# MCU.net
KiCad netlist of a schematic drawn in Altium Designer
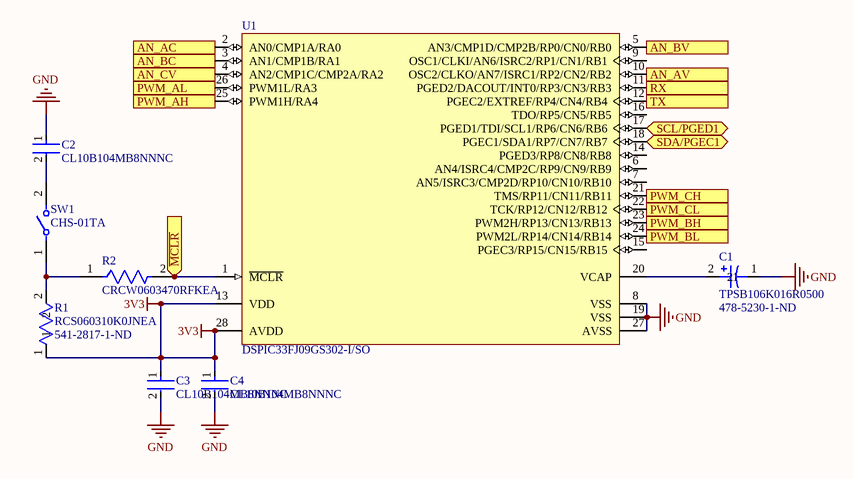
[diagram p0: MCU.SchDoc]

(export (version "E")
  (design (tool "Eeschema 10.0.6"))
  (components
    (comp (ref "C1")
      (value "TPSB106K016R0500")
      (footprint "TPSB106K016R0500")
      (description "CAP TANT 10UF 10% 16V SMD")
      (fields
        (field (name "MANUFACTURER") "Kyocera AVX")
        (field (name "TOLERANCE") "10%")
        (field (name "SUPPLIER PART NUMBER 1") "478-5230-1-ND")
      )
      (libsource (lib "Schematic Library") (part "TPSB106K016R0500"))
    )
    (comp (ref "C2")
      (value "CL10B104MB8NNNC")
      (footprint "FP-CL10-IPC_C")
      (description "Cap Ceramic 100nF 50V X7R ±20% Pad SMD 0603 +125°C T/R")
      (fields (field (name "TOLERANCE") "20%"))
      (libsource (lib "Altium Content Vault") (part "b4654b650e69147ec39a6b967a45e02"))
    )
    (comp (ref "C3")
      (value "CL10B104MB8NNNC")
      (footprint "FP-CL10-IPC_C")
      (description "Cap Ceramic 100nF 50V X7R ±20% Pad SMD 0603 +125°C T/R")
      (fields (field (name "TOLERANCE") "20%"))
      (libsource (lib "Altium Content Vault") (part "b4654b650e69147ec39a6b967a45e02"))
    )
    (comp (ref "C4")
      (value "CL10B104MB8NNNC")
      (footprint "FP-CL10-IPC_C")
      (description "Cap Ceramic 100nF 50V X7R ±20% Pad SMD 0603 +125°C T/R")
      (fields (field (name "TOLERANCE") "20%"))
      (libsource (lib "Altium Content Vault") (part "b4654b650e69147ec39a6b967a45e02"))
    )
    (comp (ref "R1")
      (value "RCS060310K0JNEA")
      (footprint "RCS060310K0JNEA")
      (description "RES SMD 10K OHM 5% 1/4W 0603")
      (fields
        (field (name "MANUFACTURER") "Vishay Dale")
        (field (name "TOLERANCE") "5%")
        (field (name "SUPPLIER PART NUMBER 1") "541-2817-1-ND")
      )
      (libsource (lib "Schematic Library") (part "RCS060310K0JNEA"))
    )
    (comp (ref "R2")
      (value "CRCW0603470RFKEA")
      (footprint "FP-CRCW0603-e3-MFG")
      (description "RES Thick Film, 470Ω, 1%, 0.1W, 100ppm/°C, 0603")
      (fields (field (name "TOLERANCE") "1%"))
      (libsource (lib "Altium Content Vault") (part "1029c3af85768c4190bb7ad29bc67b5"))
    )
    (comp (ref "SW1")
      (value "CHS-01TA")
      (footprint "FP-CHS-01TA-MFG")
      (description "SWITCH SLIDE DIP SPST 100MA 6V")
      (fields
        (field (name "OCTOPART") "https://octopart.com/chs-01ta-nidec+copal-52304644")
        (field (name "MANUFACTURER") "Nidec Copal Electronics")
      )
      (libsource (lib "Altium Content Vault") (part "bb27bde45df87f1f469753f287ef5ae"))
    )
    (comp (ref "U1")
      (value "DSPIC33FJ09GS302-I/SO")
      (footprint "MCHP-SOIC-SO28_M")
      (fields (field (name "MANUFACTURER") "Microchip"))
      (libsource (lib "Altium Content Vault") (part "MCHP-dsPIC33FJ09GS302-SOIC_SPDIP_SSOP-28"))
    )
  )
  (nets
    (net (code "1") (name "/AN_AC") (class "Default")
      (node (ref "U1") (pin "2") (pinfunction "AN0/CMP1A/RA0_2") (pintype "bidirectional"))
    )
    (net (code "2") (name "/AN_AV") (class "Default")
      (node (ref "U1") (pin "10") (pinfunction "OSC2/CLKO/AN7/ISRC1/RP2/CN2/RB2_10") (pintype "bidirectional"))
    )
    (net (code "3") (name "/AN_BC") (class "Default")
      (node (ref "U1") (pin "3") (pinfunction "AN1/CMP1B/RA1_3") (pintype "bidirectional"))
    )
    (net (code "4") (name "/AN_BV") (class "Default")
      (node (ref "U1") (pin "5") (pinfunction "AN3/CMP1D/CMP2B/RP0/CN0/RB0_5") (pintype "bidirectional"))
    )
    (net (code "5") (name "/AN_CV") (class "Default")
      (node (ref "U1") (pin "4") (pinfunction "AN2/CMP1C/CMP2A/RA2_4") (pintype "bidirectional"))
    )
    (net (code "6") (name "/PWM_AH") (class "Default")
      (node (ref "U1") (pin "25") (pinfunction "PWM1H/RA4_25") (pintype "bidirectional"))
    )
    (net (code "7") (name "/PWM_AL") (class "Default")
      (node (ref "U1") (pin "26") (pinfunction "PWM1L/RA3_26") (pintype "bidirectional"))
    )
    (net (code "8") (name "/PWM_BH") (class "Default")
      (node (ref "U1") (pin "23") (pinfunction "PWM2H/RP13/CN13/RB13_23") (pintype "bidirectional"))
    )
    (net (code "9") (name "/PWM_BL") (class "Default")
      (node (ref "U1") (pin "24") (pinfunction "PWM2L/RP14/CN14/RB14_24") (pintype "bidirectional"))
    )
    (net (code "10") (name "/PWM_CH") (class "Default")
      (node (ref "U1") (pin "21") (pinfunction "TMS/RP11/CN11/RB11_21") (pintype "bidirectional"))
    )
    (net (code "11") (name "/PWM_CL") (class "Default")
      (node (ref "U1") (pin "22") (pinfunction "TCK/RP12/CN12/RB12_22") (pintype "bidirectional"))
    )
    (net (code "12") (name "/RX") (class "Default")
      (node (ref "U1") (pin "11") (pinfunction "PGED2/DACOUT/INT0/RP3/CN3/RB3_11") (pintype "bidirectional"))
    )
    (net (code "13") (name "/SCL{slash}PGED1") (class "Default")
      (node (ref "U1") (pin "17") (pinfunction "PGED1/TDI/SCL1/RP6/CN6/RB6_17") (pintype "bidirectional"))
    )
    (net (code "14") (name "/SDA{slash}PGEC1") (class "Default")
      (node (ref "U1") (pin "18") (pinfunction "PGEC1/SDA1/RP7/CN7/RB7_18") (pintype "bidirectional"))
    )
    (net (code "15") (name "/TX") (class "Default")
      (node (ref "U1") (pin "12") (pinfunction "PGEC2/EXTREF/RP4/CN4/RB4_12") (pintype "bidirectional"))
    )
    (net (code "16") (name "/~{MCLR}") (class "Default")
      (node (ref "R2") (pin "2") (pinfunction "2_2") (pintype "passive"))
      (node (ref "U1") (pin "1") (pinfunction "~{MCLR}_1") (pintype "input"))
    )
    (net (code "17") (name "3V3") (class "Default")
      (node (ref "C3") (pin "1") (pinfunction "1_1") (pintype "passive"))
      (node (ref "C4") (pin "1") (pinfunction "1_1") (pintype "passive"))
      (node (ref "R1") (pin "1") (pinfunction "1_1") (pintype "passive"))
      (node (ref "U1") (pin "13") (pinfunction "VDD_13") (pintype "power_in"))
      (node (ref "U1") (pin "28") (pinfunction "AVDD_28") (pintype "power_in"))
    )
    (net (code "18") (name "GND") (class "Default")
      (node (ref "C1") (pin "1") (pinfunction "1_1") (pintype "passive"))
      (node (ref "C2") (pin "1") (pinfunction "1_1") (pintype "passive"))
      (node (ref "C3") (pin "2") (pinfunction "2_2") (pintype "passive"))
      (node (ref "C4") (pin "2") (pinfunction "2_2") (pintype "passive"))
      (node (ref "U1") (pin "19") (pinfunction "VSS_19") (pintype "power_in"))
      (node (ref "U1") (pin "27") (pinfunction "AVSS_27") (pintype "power_in"))
      (node (ref "U1") (pin "8") (pinfunction "VSS_8") (pintype "power_in"))
    )
    (net (code "19") (name "Net-(C2-Pad2)") (class "Default")
      (node (ref "C2") (pin "2") (pinfunction "2_2") (pintype "passive"))
      (node (ref "SW1") (pin "2") (pinfunction "2_2") (pintype "passive"))
    )
    (net (code "20") (name "Net-(R1-Pad2)") (class "Default")
      (node (ref "R1") (pin "2") (pinfunction "2_2") (pintype "passive"))
      (node (ref "R2") (pin "1") (pinfunction "1_1") (pintype "passive"))
      (node (ref "SW1") (pin "1") (pinfunction "1_1") (pintype "passive"))
    )
    (net (code "21") (name "Net-(U1-VCAP)") (class "Default")
      (node (ref "C1") (pin "2") (pinfunction "2_2") (pintype "passive"))
      (node (ref "U1") (pin "20") (pinfunction "VCAP_20") (pintype "passive"))
    )
    (net (code "22") (name "unconnected-(U1-AN4{slash}ISRC4{slash}CMP2C{slash}RP9{slash}CN9{slash}RB9-Pad6)") (class "Default")
      (node (ref "U1") (pin "6") (pinfunction "AN4/ISRC4/CMP2C/RP9/CN9/RB9_6") (pintype "bidirectional"))
    )
    (net (code "23") (name "unconnected-(U1-AN5{slash}ISRC3{slash}CMP2D{slash}RP10{slash}CN10{slash}RB10-Pad7)") (class "Default")
      (node (ref "U1") (pin "7") (pinfunction "AN5/ISRC3/CMP2D/RP10/CN10/RB10_7") (pintype "bidirectional"))
    )
    (net (code "24") (name "unconnected-(U1-OSC1{slash}CLKI{slash}AN6{slash}ISRC2{slash}RP1{slash}CN1{slash}RB1-Pad9)") (class "Default")
      (node (ref "U1") (pin "9") (pinfunction "OSC1/CLKI/AN6/ISRC2/RP1/CN1/RB1_9") (pintype "bidirectional"))
    )
    (net (code "25") (name "unconnected-(U1-PGEC3{slash}RP15{slash}CN15{slash}RB15-Pad15)") (class "Default")
      (node (ref "U1") (pin "15") (pinfunction "PGEC3/RP15/CN15/RB15_15") (pintype "bidirectional"))
    )
    (net (code "26") (name "unconnected-(U1-PGED3{slash}RP8{slash}CN8{slash}RB8-Pad14)") (class "Default")
      (node (ref "U1") (pin "14") (pinfunction "PGED3/RP8/CN8/RB8_14") (pintype "bidirectional"))
    )
    (net (code "27") (name "unconnected-(U1-TDO{slash}RP5{slash}CN5{slash}RB5-Pad16)") (class "Default")
      (node (ref "U1") (pin "16") (pinfunction "TDO/RP5/CN5/RB5_16") (pintype "bidirectional"))
    )
  )
)
